# mainBoard1.net
KiCad netlist of a schematic drawn in EAGLE
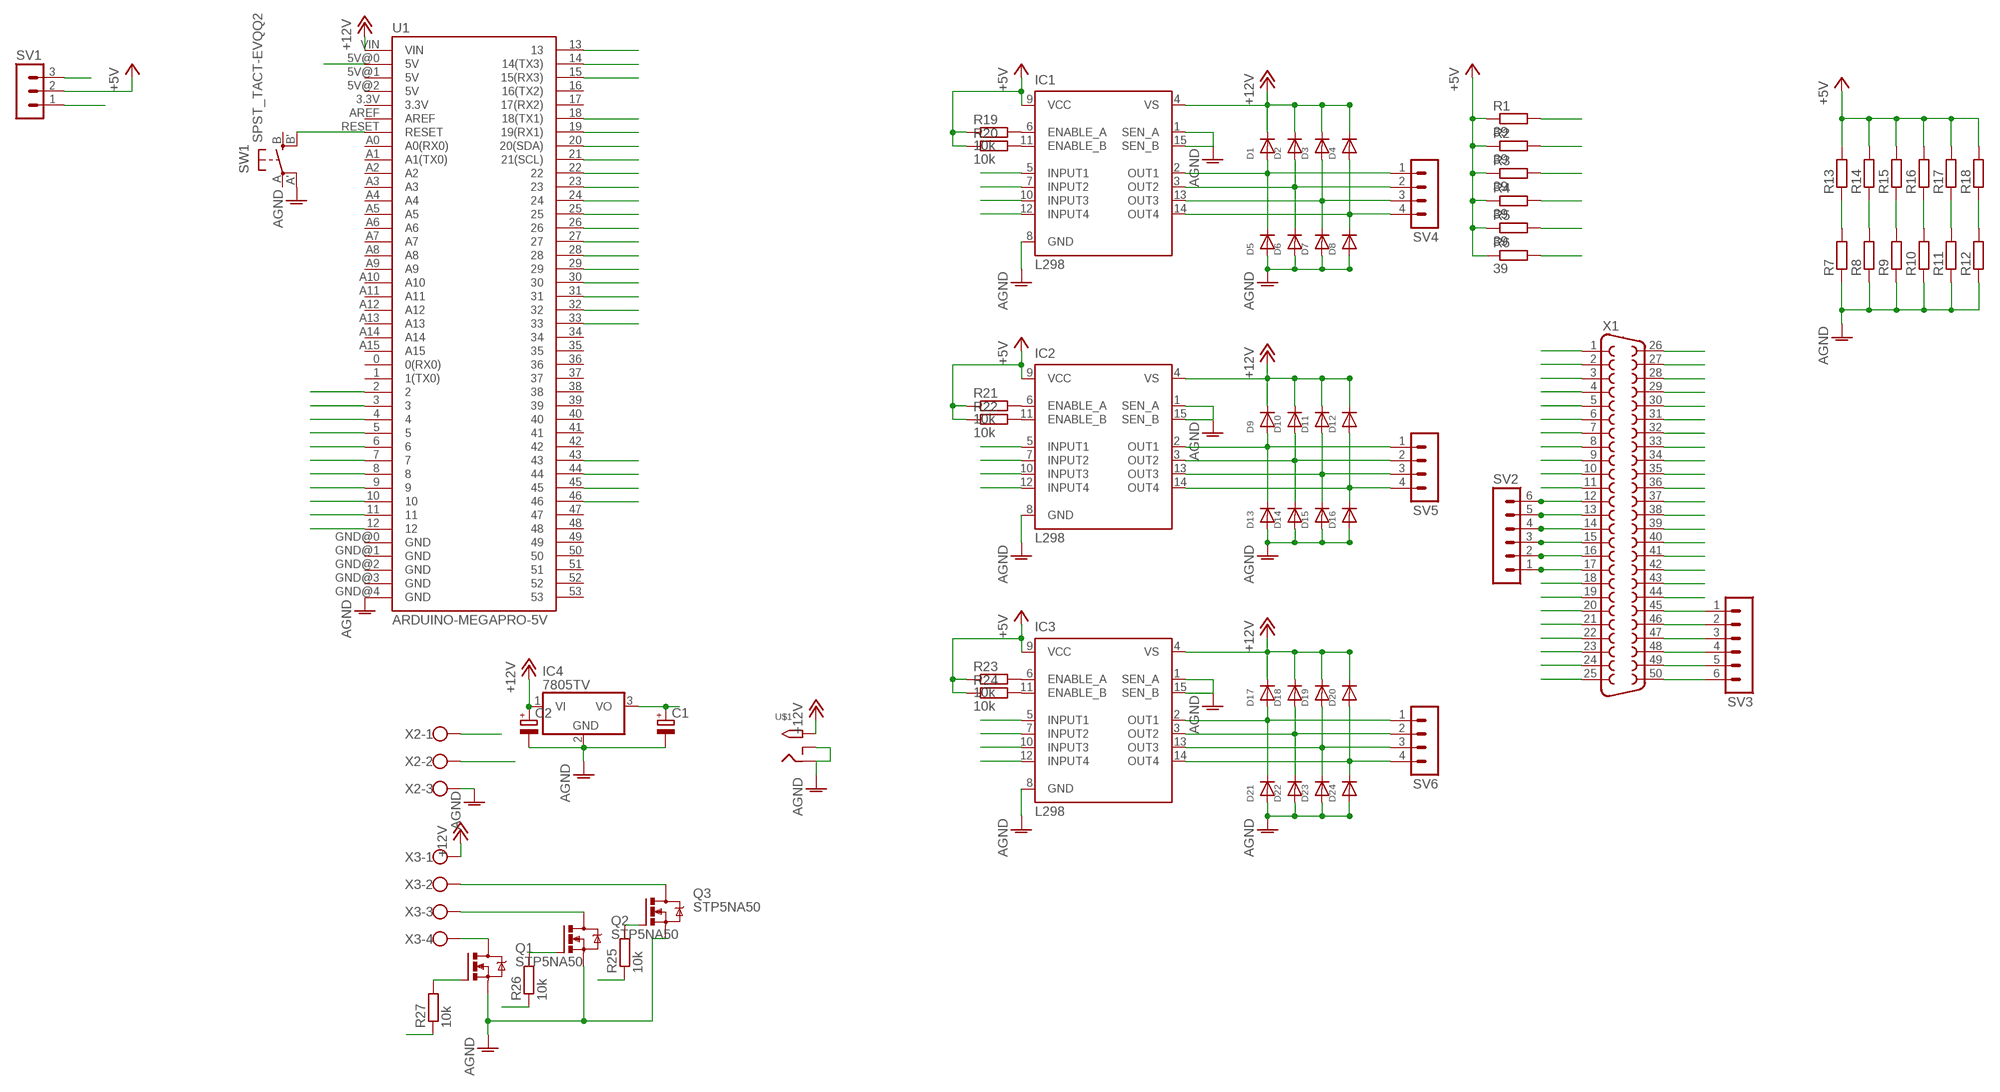
[diagram p0: schematic, sheet 1]

(export (version "E")
  (design (tool "Eeschema 10.0.6"))
  (components
    (comp (ref "C1")
      (value "CPOL-EUE2,5-6E")
      (footprint "eagle-import:E2,5-6E")
      (libsource (lib "eagle-import") (part "CPOL-EUE2,5-6E"))
    )
    (comp (ref "C2")
      (value "CPOL-EUE2,5-6E")
      (footprint "eagle-import:E2,5-6E")
      (libsource (lib "eagle-import") (part "CPOL-EUE2,5-6E"))
    )
    (comp (ref "D1")
      (value "DIODESOD-323F")
      (footprint "eagle-import:SOD-323F")
      (libsource (lib "eagle-import") (part "DIODESOD-323F"))
    )
    (comp (ref "D2")
      (value "DIODESOD-323F")
      (footprint "eagle-import:SOD-323F")
      (libsource (lib "eagle-import") (part "DIODESOD-323F"))
    )
    (comp (ref "D3")
      (value "DIODESOD-323F")
      (footprint "eagle-import:SOD-323F")
      (libsource (lib "eagle-import") (part "DIODESOD-323F"))
    )
    (comp (ref "D4")
      (value "DIODESOD-323F")
      (footprint "eagle-import:SOD-323F")
      (libsource (lib "eagle-import") (part "DIODESOD-323F"))
    )
    (comp (ref "D5")
      (value "DIODESOD-323F")
      (footprint "eagle-import:SOD-323F")
      (libsource (lib "eagle-import") (part "DIODESOD-323F"))
    )
    (comp (ref "D6")
      (value "DIODESOD-323F")
      (footprint "eagle-import:SOD-323F")
      (libsource (lib "eagle-import") (part "DIODESOD-323F"))
    )
    (comp (ref "D7")
      (value "DIODESOD-323F")
      (footprint "eagle-import:SOD-323F")
      (libsource (lib "eagle-import") (part "DIODESOD-323F"))
    )
    (comp (ref "D8")
      (value "DIODESOD-323F")
      (footprint "eagle-import:SOD-323F")
      (libsource (lib "eagle-import") (part "DIODESOD-323F"))
    )
    (comp (ref "D9")
      (value "DIODESOD-323F")
      (footprint "eagle-import:SOD-323F")
      (libsource (lib "eagle-import") (part "DIODESOD-323F"))
    )
    (comp (ref "D10")
      (value "DIODESOD-323F")
      (footprint "eagle-import:SOD-323F")
      (libsource (lib "eagle-import") (part "DIODESOD-323F"))
    )
    (comp (ref "D11")
      (value "DIODESOD-323F")
      (footprint "eagle-import:SOD-323F")
      (libsource (lib "eagle-import") (part "DIODESOD-323F"))
    )
    (comp (ref "D12")
      (value "DIODESOD-323F")
      (footprint "eagle-import:SOD-323F")
      (libsource (lib "eagle-import") (part "DIODESOD-323F"))
    )
    (comp (ref "D13")
      (value "DIODESOD-323F")
      (footprint "eagle-import:SOD-323F")
      (libsource (lib "eagle-import") (part "DIODESOD-323F"))
    )
    (comp (ref "D14")
      (value "DIODESOD-323F")
      (footprint "eagle-import:SOD-323F")
      (libsource (lib "eagle-import") (part "DIODESOD-323F"))
    )
    (comp (ref "D15")
      (value "DIODESOD-323F")
      (footprint "eagle-import:SOD-323F")
      (libsource (lib "eagle-import") (part "DIODESOD-323F"))
    )
    (comp (ref "D16")
      (value "DIODESOD-323F")
      (footprint "eagle-import:SOD-323F")
      (libsource (lib "eagle-import") (part "DIODESOD-323F"))
    )
    (comp (ref "D17")
      (value "DIODESOD-323F")
      (footprint "eagle-import:SOD-323F")
      (libsource (lib "eagle-import") (part "DIODESOD-323F"))
    )
    (comp (ref "D18")
      (value "DIODESOD-323F")
      (footprint "eagle-import:SOD-323F")
      (libsource (lib "eagle-import") (part "DIODESOD-323F"))
    )
    (comp (ref "D19")
      (value "DIODESOD-323F")
      (footprint "eagle-import:SOD-323F")
      (libsource (lib "eagle-import") (part "DIODESOD-323F"))
    )
    (comp (ref "D20")
      (value "DIODESOD-323F")
      (footprint "eagle-import:SOD-323F")
      (libsource (lib "eagle-import") (part "DIODESOD-323F"))
    )
    (comp (ref "D21")
      (value "DIODESOD-323F")
      (footprint "eagle-import:SOD-323F")
      (libsource (lib "eagle-import") (part "DIODESOD-323F"))
    )
    (comp (ref "D22")
      (value "DIODESOD-323F")
      (footprint "eagle-import:SOD-323F")
      (libsource (lib "eagle-import") (part "DIODESOD-323F"))
    )
    (comp (ref "D23")
      (value "DIODESOD-323F")
      (footprint "eagle-import:SOD-323F")
      (libsource (lib "eagle-import") (part "DIODESOD-323F"))
    )
    (comp (ref "D24")
      (value "DIODESOD-323F")
      (footprint "eagle-import:SOD-323F")
      (libsource (lib "eagle-import") (part "DIODESOD-323F"))
    )
    (comp (ref "IC1")
      (value "L298")
      (footprint "eagle-import:MULTIWATT-15")
      (fields (field (name "MPN") "L298N"))
      (libsource (lib "eagle-import") (part "L298"))
    )
    (comp (ref "IC2")
      (value "L298")
      (footprint "eagle-import:MULTIWATT-15")
      (fields (field (name "MPN") "L298N"))
      (libsource (lib "eagle-import") (part "L298"))
    )
    (comp (ref "IC3")
      (value "L298")
      (footprint "eagle-import:MULTIWATT-15")
      (fields (field (name "MPN") "L298N"))
      (libsource (lib "eagle-import") (part "L298"))
    )
    (comp (ref "IC4")
      (value "7805TV")
      (footprint "eagle-import:TO220V")
      (libsource (lib "eagle-import") (part "78TV05"))
    )
    (comp (ref "Q1")
      (value "STP5NA50")
      (footprint "eagle-import:TO220BV")
      (libsource (lib "eagle-import") (part "STP5NA50"))
    )
    (comp (ref "Q2")
      (value "STP5NA50")
      (footprint "eagle-import:TO220BV")
      (libsource (lib "eagle-import") (part "STP5NA50"))
    )
    (comp (ref "Q3")
      (value "STP5NA50")
      (footprint "eagle-import:TO220BV")
      (libsource (lib "eagle-import") (part "STP5NA50"))
    )
    (comp (ref "R1")
      (value "39")
      (footprint "eagle-import:0207_10")
      (libsource (lib "eagle-import") (part "R0207/10"))
    )
    (comp (ref "R2")
      (value "39")
      (footprint "eagle-import:0207_10")
      (libsource (lib "eagle-import") (part "R0207/10"))
    )
    (comp (ref "R3")
      (value "39")
      (footprint "eagle-import:0207_10")
      (libsource (lib "eagle-import") (part "R0207/10"))
    )
    (comp (ref "R4")
      (value "39")
      (footprint "eagle-import:0207_10")
      (libsource (lib "eagle-import") (part "R0207/10"))
    )
    (comp (ref "R5")
      (value "39")
      (footprint "eagle-import:0207_10")
      (libsource (lib "eagle-import") (part "R0207/10"))
    )
    (comp (ref "R6")
      (value "39")
      (footprint "eagle-import:0207_10")
      (libsource (lib "eagle-import") (part "R0207/10"))
    )
    (comp (ref "R7")
      (value "R0207/10")
      (footprint "eagle-import:0207_10")
      (libsource (lib "eagle-import") (part "R0207/10"))
    )
    (comp (ref "R8")
      (value "R0207/10")
      (footprint "eagle-import:0207_10")
      (libsource (lib "eagle-import") (part "R0207/10"))
    )
    (comp (ref "R9")
      (value "R0207/10")
      (footprint "eagle-import:0207_10")
      (libsource (lib "eagle-import") (part "R0207/10"))
    )
    (comp (ref "R10")
      (value "R0207/10")
      (footprint "eagle-import:0207_10")
      (libsource (lib "eagle-import") (part "R0207/10"))
    )
    (comp (ref "R11")
      (value "R0207/10")
      (footprint "eagle-import:0207_10")
      (libsource (lib "eagle-import") (part "R0207/10"))
    )
    (comp (ref "R12")
      (value "R0207/10")
      (footprint "eagle-import:0207_10")
      (libsource (lib "eagle-import") (part "R0207/10"))
    )
    (comp (ref "R13")
      (value "R0207/10")
      (footprint "eagle-import:0207_10")
      (libsource (lib "eagle-import") (part "R0207/10"))
    )
    (comp (ref "R14")
      (value "R0207/10")
      (footprint "eagle-import:0207_10")
      (libsource (lib "eagle-import") (part "R0207/10"))
    )
    (comp (ref "R15")
      (value "R0207/10")
      (footprint "eagle-import:0207_10")
      (libsource (lib "eagle-import") (part "R0207/10"))
    )
    (comp (ref "R16")
      (value "R0207/10")
      (footprint "eagle-import:0207_10")
      (libsource (lib "eagle-import") (part "R0207/10"))
    )
    (comp (ref "R17")
      (value "R0207/10")
      (footprint "eagle-import:0207_10")
      (libsource (lib "eagle-import") (part "R0207/10"))
    )
    (comp (ref "R18")
      (value "R0207/10")
      (footprint "eagle-import:0207_10")
      (libsource (lib "eagle-import") (part "R0207/10"))
    )
    (comp (ref "R19")
      (value "10k")
      (footprint "eagle-import:R0805")
      (libsource (lib "eagle-import") (part "R-EU_R0805"))
    )
    (comp (ref "R20")
      (value "10k")
      (footprint "eagle-import:R0805")
      (libsource (lib "eagle-import") (part "R-EU_R0805"))
    )
    (comp (ref "R21")
      (value "10k")
      (footprint "eagle-import:R0805")
      (libsource (lib "eagle-import") (part "R-EU_R0805"))
    )
    (comp (ref "R22")
      (value "10k")
      (footprint "eagle-import:R0805")
      (libsource (lib "eagle-import") (part "R-EU_R0805"))
    )
    (comp (ref "R23")
      (value "10k")
      (footprint "eagle-import:R0805")
      (libsource (lib "eagle-import") (part "R-EU_R0805"))
    )
    (comp (ref "R24")
      (value "10k")
      (footprint "eagle-import:R0805")
      (libsource (lib "eagle-import") (part "R-EU_R0805"))
    )
    (comp (ref "R25")
      (value "10k")
      (footprint "eagle-import:R0805")
      (libsource (lib "eagle-import") (part "R-EU_R0805"))
    )
    (comp (ref "R26")
      (value "10k")
      (footprint "eagle-import:R0805")
      (libsource (lib "eagle-import") (part "R-EU_R0805"))
    )
    (comp (ref "R27")
      (value "10k")
      (footprint "eagle-import:R0805")
      (libsource (lib "eagle-import") (part "R-EU_R0805"))
    )
    (comp (ref "SV1")
      (value "MA03-1")
      (footprint "eagle-import:MA03-1")
      (libsource (lib "eagle-import") (part "MA03-1"))
    )
    (comp (ref "SV2")
      (value "MA06-1")
      (footprint "eagle-import:MA06-1")
      (libsource (lib "eagle-import") (part "MA06-1"))
    )
    (comp (ref "SV3")
      (value "MA06-1")
      (footprint "eagle-import:MA06-1")
      (libsource (lib "eagle-import") (part "MA06-1"))
    )
    (comp (ref "SV4")
      (value "MA04-1")
      (footprint "eagle-import:MA04-1")
      (libsource (lib "eagle-import") (part "MA04-1"))
    )
    (comp (ref "SV5")
      (value "MA04-1")
      (footprint "eagle-import:MA04-1")
      (libsource (lib "eagle-import") (part "MA04-1"))
    )
    (comp (ref "SV6")
      (value "MA04-1")
      (footprint "eagle-import:MA04-1")
      (libsource (lib "eagle-import") (part "MA04-1"))
    )
    (comp (ref "SW1")
      (value "SPST_TACT-EVQQ2")
      (footprint "eagle-import:EVQ-Q2")
      (libsource (lib "eagle-import") (part "SPST_TACT-EVQQ2"))
    )
    (comp (ref "U$1")
      (value "2.1MMJACKTHM")
      (footprint "eagle-import:PJ-102A")
      (libsource (lib "eagle-import") (part "2.1MMJACKTHM"))
    )
    (comp (ref "U1")
      (value "ARDUINO-MEGAPRO-5V")
      (footprint "eagle-import:ARDUINO_MEGA-PRO-5V")
      (libsource (lib "eagle-import") (part "ARDUINO-MEGAPRO-5V"))
    )
    (comp (ref "X1")
      (value "F50VP")
      (footprint "eagle-import:F50VP")
      (libsource (lib "eagle-import") (part "F50VP"))
    )
    (comp (ref "X2")
      (value "W237-103")
      (footprint "eagle-import:W237-103")
      (fields (field (name "MPN") "237-103"))
      (libsource (lib "eagle-import") (part "W237-103"))
    )
    (comp (ref "X3")
      (value "W237-4")
      (footprint "eagle-import:W237-4")
      (libsource (lib "eagle-import") (part "W237-4"))
    )
  )
  (nets
    (net (code "1") (name "+5V") (class "Default")
      (node (ref "IC1") (pin "9") (pinfunction "VCC_9") (pintype "power_in"))
      (node (ref "IC2") (pin "9") (pinfunction "VCC_9") (pintype "power_in"))
      (node (ref "IC3") (pin "9") (pinfunction "VCC_9") (pintype "power_in"))
      (node (ref "R1") (pin "1") (pinfunction "1_1") (pintype "passive"))
      (node (ref "R13") (pin "2") (pinfunction "2_2") (pintype "passive"))
      (node (ref "R14") (pin "2") (pinfunction "2_2") (pintype "passive"))
      (node (ref "R15") (pin "2") (pinfunction "2_2") (pintype "passive"))
      (node (ref "R16") (pin "2") (pinfunction "2_2") (pintype "passive"))
      (node (ref "R17") (pin "2") (pinfunction "2_2") (pintype "passive"))
      (node (ref "R18") (pin "2") (pinfunction "2_2") (pintype "passive"))
      (node (ref "R19") (pin "1") (pinfunction "1_1") (pintype "passive"))
      (node (ref "R2") (pin "1") (pinfunction "1_1") (pintype "passive"))
      (node (ref "R20") (pin "1") (pinfunction "1_1") (pintype "passive"))
      (node (ref "R21") (pin "1") (pinfunction "1_1") (pintype "passive"))
      (node (ref "R22") (pin "1") (pinfunction "1_1") (pintype "passive"))
      (node (ref "R23") (pin "1") (pinfunction "1_1") (pintype "passive"))
      (node (ref "R24") (pin "1") (pinfunction "1_1") (pintype "passive"))
      (node (ref "R3") (pin "1") (pinfunction "1_1") (pintype "passive"))
      (node (ref "R4") (pin "1") (pinfunction "1_1") (pintype "passive"))
      (node (ref "R5") (pin "1") (pinfunction "1_1") (pintype "passive"))
      (node (ref "R6") (pin "1") (pinfunction "1_1") (pintype "passive"))
      (node (ref "SV1") (pin "2") (pinfunction "2_2") (pintype "passive"))
    )
    (net (code "2") (name "+12V") (class "Default")
      (node (ref "C2") (pin "+") (pinfunction "+_+") (pintype "passive"))
      (node (ref "D1") (pin "C") (pinfunction "C_C") (pintype "passive"))
      (node (ref "D10") (pin "C") (pinfunction "C_C") (pintype "passive"))
      (node (ref "D11") (pin "C") (pinfunction "C_C") (pintype "passive"))
      (node (ref "D12") (pin "C") (pinfunction "C_C") (pintype "passive"))
      (node (ref "D17") (pin "C") (pinfunction "C_C") (pintype "passive"))
      (node (ref "D18") (pin "C") (pinfunction "C_C") (pintype "passive"))
      (node (ref "D19") (pin "C") (pinfunction "C_C") (pintype "passive"))
      (node (ref "D2") (pin "C") (pinfunction "C_C") (pintype "passive"))
      (node (ref "D20") (pin "C") (pinfunction "C_C") (pintype "passive"))
      (node (ref "D3") (pin "C") (pinfunction "C_C") (pintype "passive"))
      (node (ref "D4") (pin "C") (pinfunction "C_C") (pintype "passive"))
      (node (ref "D9") (pin "C") (pinfunction "C_C") (pintype "passive"))
      (node (ref "IC1") (pin "4") (pinfunction "VS_4") (pintype "power_in"))
      (node (ref "IC2") (pin "4") (pinfunction "VS_4") (pintype "power_in"))
      (node (ref "IC3") (pin "4") (pinfunction "VS_4") (pintype "power_in"))
      (node (ref "IC4") (pin "1") (pinfunction "VI_1") (pintype "input"))
      (node (ref "U$1") (pin "TIP") (pinfunction "TIP_TIP") (pintype "bidirectional"))
      (node (ref "U1") (pin "VIN") (pinfunction "VIN_VIN") (pintype "bidirectional"))
      (node (ref "X3") (pin "1") (pinfunction "KL_1") (pintype "passive"))
    )
    (net (code "3") (name "/5V_ARD") (class "Default")
      (node (ref "SV1") (pin "3") (pinfunction "3_3") (pintype "passive"))
      (node (ref "U1") (pin "5V@0") (pinfunction "5V_5V@0") (pintype "bidirectional"))
    )
    (net (code "4") (name "/5V_REG") (class "Default")
      (node (ref "C1") (pin "+") (pinfunction "+_+") (pintype "passive"))
      (node (ref "IC4") (pin "3") (pinfunction "VO_3") (pintype "passive"))
      (node (ref "SV1") (pin "1") (pinfunction "1_1") (pintype "passive"))
      (node (ref "X2") (pin "1") (pinfunction "KL_1") (pintype "passive"))
    )
    (net (code "5") (name "/LED_0") (class "Default")
      (node (ref "R1") (pin "2") (pinfunction "2_2") (pintype "passive"))
      (node (ref "X1") (pin "11") (pinfunction "11_11") (pintype "passive"))
    )
    (net (code "6") (name "/LED_1") (class "Default")
      (node (ref "R2") (pin "2") (pinfunction "2_2") (pintype "passive"))
      (node (ref "X1") (pin "27") (pinfunction "27_27") (pintype "passive"))
    )
    (net (code "7") (name "/LED_2") (class "Default")
      (node (ref "R3") (pin "2") (pinfunction "2_2") (pintype "passive"))
      (node (ref "X1") (pin "10") (pinfunction "10_10") (pintype "passive"))
    )
    (net (code "8") (name "/LED_3") (class "Default")
      (node (ref "R4") (pin "2") (pinfunction "2_2") (pintype "passive"))
      (node (ref "X1") (pin "26") (pinfunction "26_26") (pintype "passive"))
    )
    (net (code "9") (name "/LED_4") (class "Default")
      (node (ref "R5") (pin "2") (pinfunction "2_2") (pintype "passive"))
      (node (ref "X1") (pin "9") (pinfunction "9_9") (pintype "passive"))
    )
    (net (code "10") (name "/LED_5") (class "Default")
      (node (ref "R6") (pin "2") (pinfunction "2_2") (pintype "passive"))
      (node (ref "X1") (pin "25") (pinfunction "25_25") (pintype "passive"))
    )
    (net (code "11") (name "/LED_B") (class "Default")
      (node (ref "R27") (pin "1") (pinfunction "1_1") (pintype "passive"))
      (node (ref "U1") (pin "46") (pinfunction "46_46") (pintype "bidirectional"))
    )
    (net (code "12") (name "/LED_DATA") (class "Default")
      (node (ref "U1") (pin "43") (pinfunction "43_43") (pintype "bidirectional"))
      (node (ref "X2") (pin "2") (pinfunction "KL_2") (pintype "passive"))
    )
    (net (code "13") (name "/LED_G") (class "Default")
      (node (ref "R26") (pin "1") (pinfunction "1_1") (pintype "passive"))
      (node (ref "U1") (pin "45") (pinfunction "45_45") (pintype "bidirectional"))
    )
    (net (code "14") (name "/LED_R") (class "Default")
      (node (ref "R25") (pin "1") (pinfunction "1_1") (pintype "passive"))
      (node (ref "U1") (pin "44") (pinfunction "44_44") (pintype "bidirectional"))
    )
    (net (code "15") (name "/M1_0") (class "Default")
      (node (ref "D1") (pin "A") (pinfunction "A_A") (pintype "passive"))
      (node (ref "D5") (pin "C") (pinfunction "C_C") (pintype "passive"))
      (node (ref "IC1") (pin "2") (pinfunction "OUT1_2") (pintype "output"))
      (node (ref "SV3") (pin "6") (pinfunction "6_6") (pintype "passive"))
      (node (ref "SV4") (pin "1") (pinfunction "1_1") (pintype "passive"))
      (node (ref "X1") (pin "50") (pinfunction "50_50") (pintype "passive"))
    )
    (net (code "16") (name "/M1_0_IN") (class "Default")
      (node (ref "IC1") (pin "5") (pinfunction "INPUT1_5") (pintype "input"))
      (node (ref "U1") (pin "14") (pinfunction "14(TX3)_14") (pintype "bidirectional"))
    )
    (net (code "17") (name "/M1_1") (class "Default")
      (node (ref "D3") (pin "A") (pinfunction "A_A") (pintype "passive"))
      (node (ref "D7") (pin "C") (pinfunction "C_C") (pintype "passive"))
      (node (ref "IC1") (pin "13") (pinfunction "OUT3_13") (pintype "output"))
      (node (ref "SV3") (pin "5") (pinfunction "5_5") (pintype "passive"))
      (node (ref "SV4") (pin "3") (pinfunction "3_3") (pintype "passive"))
      (node (ref "X1") (pin "49") (pinfunction "49_49") (pintype "passive"))
    )
    (net (code "18") (name "/M1_1_IN") (class "Default")
      (node (ref "IC1") (pin "10") (pinfunction "INPUT3_10") (pintype "input"))
      (node (ref "U1") (pin "4") (pinfunction "4_4") (pintype "bidirectional"))
    )
    (net (code "19") (name "/M1_2") (class "Default")
      (node (ref "D13") (pin "C") (pinfunction "C_C") (pintype "passive"))
      (node (ref "D9") (pin "A") (pinfunction "A_A") (pintype "passive"))
      (node (ref "IC2") (pin "2") (pinfunction "OUT1_2") (pintype "output"))
      (node (ref "SV3") (pin "4") (pinfunction "4_4") (pintype "passive"))
      (node (ref "SV5") (pin "1") (pinfunction "1_1") (pintype "passive"))
      (node (ref "X1") (pin "48") (pinfunction "48_48") (pintype "passive"))
    )
    (net (code "20") (name "/M1_2_IN") (class "Default")
      (node (ref "IC2") (pin "5") (pinfunction "INPUT1_5") (pintype "input"))
      (node (ref "U1") (pin "6") (pinfunction "6_6") (pintype "bidirectional"))
    )
    (net (code "21") (name "/M1_3") (class "Default")
      (node (ref "D11") (pin "A") (pinfunction "A_A") (pintype "passive"))
      (node (ref "D15") (pin "C") (pinfunction "C_C") (pintype "passive"))
      (node (ref "IC2") (pin "13") (pinfunction "OUT3_13") (pintype "output"))
      (node (ref "SV3") (pin "3") (pinfunction "3_3") (pintype "passive"))
      (node (ref "SV5") (pin "3") (pinfunction "3_3") (pintype "passive"))
      (node (ref "X1") (pin "47") (pinfunction "47_47") (pintype "passive"))
    )
    (net (code "22") (name "/M1_3_IN") (class "Default")
      (node (ref "IC2") (pin "10") (pinfunction "INPUT3_10") (pintype "input"))
      (node (ref "U1") (pin "8") (pinfunction "8_8") (pintype "bidirectional"))
    )
    (net (code "23") (name "/M1_4") (class "Default")
      (node (ref "D17") (pin "A") (pinfunction "A_A") (pintype "passive"))
      (node (ref "D21") (pin "C") (pinfunction "C_C") (pintype "passive"))
      (node (ref "IC3") (pin "2") (pinfunction "OUT1_2") (pintype "output"))
      (node (ref "SV3") (pin "2") (pinfunction "2_2") (pintype "passive"))
      (node (ref "SV6") (pin "1") (pinfunction "1_1") (pintype "passive"))
      (node (ref "X1") (pin "46") (pinfunction "46_46") (pintype "passive"))
    )
    (net (code "24") (name "/M1_4_IN") (class "Default")
      (node (ref "IC3") (pin "5") (pinfunction "INPUT1_5") (pintype "input"))
      (node (ref "U1") (pin "10") (pinfunction "10_10") (pintype "bidirectional"))
    )
    (net (code "25") (name "/M1_5") (class "Default")
      (node (ref "D19") (pin "A") (pinfunction "A_A") (pintype "passive"))
      (node (ref "D23") (pin "C") (pinfunction "C_C") (pintype "passive"))
      (node (ref "IC3") (pin "13") (pinfunction "OUT3_13") (pintype "output"))
      (node (ref "SV3") (pin "1") (pinfunction "1_1") (pintype "passive"))
      (node (ref "SV6") (pin "3") (pinfunction "3_3") (pintype "passive"))
      (node (ref "X1") (pin "45") (pinfunction "45_45") (pintype "passive"))
    )
    (net (code "26") (name "/M1_5_IN") (class "Default")
      (node (ref "IC3") (pin "10") (pinfunction "INPUT3_10") (pintype "input"))
      (node (ref "U1") (pin "12") (pinfunction "12_12") (pintype "bidirectional"))
    )
    (net (code "27") (name "/M2_0") (class "Default")
      (node (ref "D2") (pin "A") (pinfunction "A_A") (pintype "passive"))
      (node (ref "D6") (pin "C") (pinfunction "C_C") (pintype "passive"))
      (node (ref "IC1") (pin "3") (pinfunction "OUT2_3") (pintype "output"))
      (node (ref "SV2") (pin "1") (pinfunction "1_1") (pintype "passive"))
      (node (ref "SV4") (pin "2") (pinfunction "2_2") (pintype "passive"))
      (node (ref "X1") (pin "17") (pinfunction "17_17") (pintype "passive"))
    )
    (net (code "28") (name "/M2_0_IN") (class "Default")
      (node (ref "IC1") (pin "7") (pinfunction "INPUT2_7") (pintype "input"))
      (node (ref "U1") (pin "15") (pinfunction "15(RX3)_15") (pintype "bidirectional"))
    )
    (net (code "29") (name "/M2_1") (class "Default")
      (node (ref "D4") (pin "A") (pinfunction "A_A") (pintype "passive"))
      (node (ref "D8") (pin "C") (pinfunction "C_C") (pintype "passive"))
      (node (ref "IC1") (pin "14") (pinfunction "OUT4_14") (pintype "output"))
      (node (ref "SV2") (pin "2") (pinfunction "2_2") (pintype "passive"))
      (node (ref "SV4") (pin "4") (pinfunction "4_4") (pintype "passive"))
      (node (ref "X1") (pin "16") (pinfunction "16_16") (pintype "passive"))
    )
    (net (code "30") (name "/M2_1_IN") (class "Default")
      (node (ref "IC1") (pin "12") (pinfunction "INPUT4_12") (pintype "input"))
      (node (ref "U1") (pin "5") (pinfunction "5_5") (pintype "bidirectional"))
    )
    (net (code "31") (name "/M2_2") (class "Default")
      (node (ref "D10") (pin "A") (pinfunction "A_A") (pintype "passive"))
      (node (ref "D14") (pin "C") (pinfunction "C_C") (pintype "passive"))
      (node (ref "IC2") (pin "3") (pinfunction "OUT2_3") (pintype "output"))
      (node (ref "SV2") (pin "3") (pinfunction "3_3") (pintype "passive"))
      (node (ref "SV5") (pin "2") (pinfunction "2_2") (pintype "passive"))
      (node (ref "X1") (pin "15") (pinfunction "15_15") (pintype "passive"))
    )
    (net (code "32") (name "/M2_2_IN") (class "Default")
      (node (ref "IC2") (pin "7") (pinfunction "INPUT2_7") (pintype "input"))
      (node (ref "U1") (pin "7") (pinfunction "7_7") (pintype "bidirectional"))
    )
    (net (code "33") (name "/M2_3") (class "Default")
      (node (ref "D12") (pin "A") (pinfunction "A_A") (pintype "passive"))
      (node (ref "D16") (pin "C") (pinfunction "C_C") (pintype "passive"))
      (node (ref "IC2") (pin "14") (pinfunction "OUT4_14") (pintype "output"))
      (node (ref "SV2") (pin "4") (pinfunction "4_4") (pintype "passive"))
      (node (ref "SV5") (pin "4") (pinfunction "4_4") (pintype "passive"))
      (node (ref "X1") (pin "14") (pinfunction "14_14") (pintype "passive"))
    )
    (net (code "34") (name "/M2_3_IN") (class "Default")
      (node (ref "IC2") (pin "12") (pinfunction "INPUT4_12") (pintype "input"))
      (node (ref "U1") (pin "9") (pinfunction "9_9") (pintype "bidirectional"))
    )
    (net (code "35") (name "/M2_4") (class "Default")
      (node (ref "D18") (pin "A") (pinfunction "A_A") (pintype "passive"))
      (node (ref "D22") (pin "C") (pinfunction "C_C") (pintype "passive"))
      (node (ref "IC3") (pin "3") (pinfunction "OUT2_3") (pintype "output"))
      (node (ref "SV2") (pin "5") (pinfunction "5_5") (pintype "passive"))
      (node (ref "SV6") (pin "2") (pinfunction "2_2") (pintype "passive"))
      (node (ref "X1") (pin "13") (pinfunction "13_13") (pintype "passive"))
    )
    (net (code "36") (name "/M2_4_IN") (class "Default")
      (node (ref "IC3") (pin "7") (pinfunction "INPUT2_7") (pintype "input"))
      (node (ref "U1") (pin "11") (pinfunction "11_11") (pintype "bidirectional"))
    )
    (net (code "37") (name "/M2_5") (class "Default")
      (node (ref "D20") (pin "A") (pinfunction "A_A") (pintype "passive"))
      (node (ref "D24") (pin "C") (pinfunction "C_C") (pintype "passive"))
      (node (ref "IC3") (pin "14") (pinfunction "OUT4_14") (pintype "output"))
      (node (ref "SV2") (pin "6") (pinfunction "6_6") (pintype "passive"))
      (node (ref "SV6") (pin "4") (pinfunction "4_4") (pintype "passive"))
      (node (ref "X1") (pin "12") (pinfunction "12_12") (pintype "passive"))
    )
    (net (code "38") (name "/M2_5_IN") (class "Default")
      (node (ref "IC3") (pin "12") (pinfunction "INPUT4_12") (pintype "input"))
      (node (ref "U1") (pin "13") (pinfunction "13_13") (pintype "bidirectional"))
    )
    (net (code "39") (name "/MS_0") (class "Default")
      (node (ref "R13") (pin "1") (pinfunction "1_1") (pintype "passive"))
      (node (ref "R7") (pin "2") (pinfunction "2_2") (pintype "passive"))
      (node (ref "U1") (pin "2") (pinfunction "2_2") (pintype "bidirectional"))
      (node (ref "X1") (pin "23") (pinfunction "23_23") (pintype "passive"))
    )
    (net (code "40") (name "/MS_1") (class "Default")
      (node (ref "R14") (pin "1") (pinfunction "1_1") (pintype "passive"))
      (node (ref "R8") (pin "2") (pinfunction "2_2") (pintype "passive"))
      (node (ref "U1") (pin "3") (pinfunction "3_3") (pintype "bidirectional"))
      (node (ref "X1") (pin "7") (pinfunction "7_7") (pintype "passive"))
    )
    (net (code "41") (name "/MS_2") (class "Default")
      (node (ref "R15") (pin "1") (pinfunction "1_1") (pintype "passive"))
      (node (ref "R9") (pin "2") (pinfunction "2_2") (pintype "passive"))
      (node (ref "U1") (pin "21") (pinfunction "21(SCL)_21") (pintype "bidirectional"))
      (node (ref "X1") (pin "24") (pinfunction "24_24") (pintype "passive"))
    )
    (net (code "42") (name "/MS_3") (class "Default")
      (node (ref "R10") (pin "2") (pinfunction "2_2") (pintype "passive"))
      (node (ref "R16") (pin "1") (pinfunction "1_1") (pintype "passive"))
      (node (ref "U1") (pin "20") (pinfunction "20(SDA)_20") (pintype "bidirectional"))
      (node (ref "X1") (pin "8") (pinfunction "8_8") (pintype "passive"))
    )
    (net (code "43") (name "/MS_4") (class "Default")
      (node (ref "R11") (pin "2") (pinfunction "2_2") (pintype "passive"))
      (node (ref "R17") (pin "1") (pinfunction "1_1") (pintype "passive"))
      (node (ref "U1") (pin "19") (pinfunction "19(RX1)_19") (pintype "bidirectional"))
      (node (ref "X1") (pin "6") (pinfunction "6_6") (pintype "passive"))
    )
    (net (code "44") (name "/MS_5") (class "Default")
      (node (ref "R12") (pin "2") (pinfunction "2_2") (pintype "passive"))
      (node (ref "R18") (pin "1") (pinfunction "1_1") (pintype "passive"))
      (node (ref "U1") (pin "18") (pinfunction "18(TX1)_18") (pintype "bidirectional"))
      (node (ref "X1") (pin "22") (pinfunction "22_22") (pintype "passive"))
    )
    (net (code "45") (name "/P0_0") (class "Default")
      (node (ref "U1") (pin "22") (pinfunction "22_22") (pintype "bidirectional"))
      (node (ref "X1") (pin "2") (pinfunction "2_2") (pintype "passive"))
    )
    (net (code "46") (name "/P0_1") (class "Default")
      (node (ref "U1") (pin "24") (pinfunction "24_24") (pintype "bidirectional"))
      (node (ref "X1") (pin "1") (pinfunction "1_1") (pintype "passive"))
    )
    (net (code "47") (name "/P0_2") (class "Default")
      (node (ref "U1") (pin "26") (pinfunction "26_26") (pintype "bidirectional"))
      (node (ref "X1") (pin "36") (pinfunction "36_36") (pintype "passive"))
    )
    (net (code "48") (name "/P0_3") (class "Default")
      (node (ref "U1") (pin "28") (pinfunction "28_28") (pintype "bidirectional"))
      (node (ref "X1") (pin "35") (pinfunction "35_35") (pintype "passive"))
    )
    (net (code "49") (name "/P0_4") (class "Default")
      (node (ref "U1") (pin "30") (pinfunction "30_30") (pintype "bidirectional"))
      (node (ref "X1") (pin "18") (pinfunction "18_18") (pintype "passive"))
    )
    (net (code "50") (name "/P0_5") (class "Default")
      (node (ref "U1") (pin "32") (pinfunction "32_32") (pintype "bidirectional"))
      (node (ref "X1") (pin "34") (pinfunction "34_34") (pintype "passive"))
    )
    (net (code "51") (name "/P1_0") (class "Default")
      (node (ref "U1") (pin "23") (pinfunction "23_23") (pintype "bidirectional"))
      (node (ref "X1") (pin "5") (pinfunction "5_5") (pintype "passive"))
    )
    (net (code "52") (name "/P1_1") (class "Default")
      (node (ref "U1") (pin "25") (pinfunction "25_25") (pintype "bidirectional"))
      (node (ref "X1") (pin "21") (pinfunction "21_21") (pintype "passive"))
    )
    (net (code "53") (name "/P1_2") (class "Default")
      (node (ref "U1") (pin "27") (pinfunction "27_27") (pintype "bidirectional"))
      (node (ref "X1") (pin "4") (pinfunction "4_4") (pintype "passive"))
    )
    (net (code "54") (name "/P1_3") (class "Default")
      (node (ref "U1") (pin "29") (pinfunction "29_29") (pintype "bidirectional"))
      (node (ref "X1") (pin "20") (pinfunction "20_20") (pintype "passive"))
    )
    (net (code "55") (name "/P1_4") (class "Default")
      (node (ref "U1") (pin "31") (pinfunction "31_31") (pintype "bidirectional"))
      (node (ref "X1") (pin "3") (pinfunction "3_3") (pintype "passive"))
    )
    (net (code "56") (name "/P1_5") (class "Default")
      (node (ref "U1") (pin "33") (pinfunction "33_33") (pintype "bidirectional"))
      (node (ref "X1") (pin "19") (pinfunction "19_19") (pintype "passive"))
    )
    (net (code "57") (name "AGND") (class "Default")
      (node (ref "C1") (pin "-") (pinfunction "-_-") (pintype "passive"))
      (node (ref "C2") (pin "-") (pinfunction "-_-") (pintype "passive"))
      (node (ref "D13") (pin "A") (pinfunction "A_A") (pintype "passive"))
      (node (ref "D14") (pin "A") (pinfunction "A_A") (pintype "passive"))
      (node (ref "D15") (pin "A") (pinfunction "A_A") (pintype "passive"))
      (node (ref "D16") (pin "A") (pinfunction "A_A") (pintype "passive"))
      (node (ref "D21") (pin "A") (pinfunction "A_A") (pintype "passive"))
      (node (ref "D22") (pin "A") (pinfunction "A_A") (pintype "passive"))
      (node (ref "D23") (pin "A") (pinfunction "A_A") (pintype "passive"))
      (node (ref "D24") (pin "A") (pinfunction "A_A") (pintype "passive"))
      (node (ref "D5") (pin "A") (pinfunction "A_A") (pintype "passive"))
      (node (ref "D6") (pin "A") (pinfunction "A_A") (pintype "passive"))
      (node (ref "D7") (pin "A") (pinfunction "A_A") (pintype "passive"))
      (node (ref "D8") (pin "A") (pinfunction "A_A") (pintype "passive"))
      (node (ref "IC1") (pin "1") (pinfunction "SEN_A_1") (pintype "input"))
      (node (ref "IC1") (pin "15") (pinfunction "SEN_B_15") (pintype "input"))
      (node (ref "IC1") (pin "8") (pinfunction "GND_8") (pintype "power_in"))
      (node (ref "IC2") (pin "1") (pinfunction "SEN_A_1") (pintype "input"))
      (node (ref "IC2") (pin "15") (pinfunction "SEN_B_15") (pintype "input"))
      (node (ref "IC2") (pin "8") (pinfunction "GND_8") (pintype "power_in"))
      (node (ref "IC3") (pin "1") (pinfunction "SEN_A_1") (pintype "input"))
      (node (ref "IC3") (pin "15") (pinfunction "SEN_B_15") (pintype "input"))
      (node (ref "IC3") (pin "8") (pinfunction "GND_8") (pintype "power_in"))
      (node (ref "IC4") (pin "2") (pinfunction "GND_2") (pintype "passive"))
      (node (ref "Q1") (pin "S") (pinfunction "S_S") (pintype "passive"))
      (node (ref "Q2") (pin "S") (pinfunction "S_S") (pintype "passive"))
      (node (ref "Q3") (pin "S") (pinfunction "S_S") (pintype "passive"))
      (node (ref "R10") (pin "1") (pinfunction "1_1") (pintype "passive"))
      (node (ref "R11") (pin "1") (pinfunction "1_1") (pintype "passive"))
      (node (ref "R12") (pin "1") (pinfunction "1_1") (pintype "passive"))
      (node (ref "R7") (pin "1") (pinfunction "1_1") (pintype "passive"))
      (node (ref "R8") (pin "1") (pinfunction "1_1") (pintype "passive"))
      (node (ref "R9") (pin "1") (pinfunction "1_1") (pintype "passive"))
      (node (ref "SW1") (pin "A'") (pinfunction "P1_A'") (pintype "passive"))
      (node (ref "U$1") (pin "RING") (pinfunction "RING_RING") (pintype "bidirectional"))
      (node (ref "U$1") (pin "RING_SW") (pinfunction "RING_SW_RING_SW") (pintype "bidirectional"))
      (node (ref "U1") (pin "GND@4") (pinfunction "GND_GND@4") (pintype "bidirectional"))
      (node (ref "X1") (pin "28") (pinfunction "28_28") (pintype "passive"))
      (node (ref "X1") (pin "29") (pinfunction "29_29") (pintype "passive"))
      (node (ref "X1") (pin "30") (pinfunction "30_30") (pintype "passive"))
      (node (ref "X1") (pin "31") (pinfunction "31_31") (pintype "passive"))
      (node (ref "X1") (pin "32") (pinfunction "32_32") (pintype "passive"))
      (node (ref "X1") (pin "33") (pinfunction "33_33") (pintype "passive"))
      (node (ref "X2") (pin "3") (pinfunction "KL_3") (pintype "passive"))
    )
    (net (code "58") (name "Net-(IC1-ENABLE_A)") (class "Default")
      (node (ref "IC1") (pin "6") (pinfunction "ENABLE_A_6") (pintype "input"))
      (node (ref "R19") (pin "2") (pinfunction "2_2") (pintype "passive"))
    )
    (net (code "59") (name "Net-(IC1-ENABLE_B)") (class "Default")
      (node (ref "IC1") (pin "11") (pinfunction "ENABLE_B_11") (pintype "input"))
      (node (ref "R20") (pin "2") (pinfunction "2_2") (pintype "passive"))
    )
    (net (code "60") (name "Net-(IC2-ENABLE_A)") (class "Default")
      (node (ref "IC2") (pin "6") (pinfunction "ENABLE_A_6") (pintype "input"))
      (node (ref "R21") (pin "2") (pinfunction "2_2") (pintype "passive"))
    )
    (net (code "61") (name "Net-(IC2-ENABLE_B)") (class "Default")
      (node (ref "IC2") (pin "11") (pinfunction "ENABLE_B_11") (pintype "input"))
      (node (ref "R22") (pin "2") (pinfunction "2_2") (pintype "passive"))
    )
    (net (code "62") (name "Net-(IC3-ENABLE_A)") (class "Default")
      (node (ref "IC3") (pin "6") (pinfunction "ENABLE_A_6") (pintype "input"))
      (node (ref "R23") (pin "2") (pinfunction "2_2") (pintype "passive"))
    )
    (net (code "63") (name "Net-(IC3-ENABLE_B)") (class "Default")
      (node (ref "IC3") (pin "11") (pinfunction "ENABLE_B_11") (pintype "input"))
      (node (ref "R24") (pin "2") (pinfunction "2_2") (pintype "passive"))
    )
    (net (code "64") (name "Net-(Q1-PadG)") (class "Default")
      (node (ref "Q1") (pin "G") (pinfunction "G_G") (pintype "passive"))
      (node (ref "R27") (pin "2") (pinfunction "2_2") (pintype "passive"))
    )
    (net (code "65") (name "Net-(Q2-PadG)") (class "Default")
      (node (ref "Q2") (pin "G") (pinfunction "G_G") (pintype "passive"))
      (node (ref "R26") (pin "2") (pinfunction "2_2") (pintype "passive"))
    )
    (net (code "66") (name "Net-(Q3-PadG)") (class "Default")
      (node (ref "Q3") (pin "G") (pinfunction "G_G") (pintype "passive"))
      (node (ref "R25") (pin "2") (pinfunction "2_2") (pintype "passive"))
    )
    (net (code "67") (name "Net-(SW1-S1)") (class "Default")
      (node (ref "SW1") (pin "B'") (pinfunction "S1_B'") (pintype "passive"))
      (node (ref "U1") (pin "RESET") (pinfunction "RESET_RESET") (pintype "bidirectional"))
    )
    (net (code "68") (name "Net-(X3B-KL)") (class "Default")
      (node (ref "Q3") (pin "D") (pinfunction "D_D") (pintype "passive"))
      (node (ref "X3") (pin "2") (pinfunction "KL_2") (pintype "passive"))
    )
    (net (code "69") (name "Net-(X3C-KL)") (class "Default")
      (node (ref "Q2") (pin "D") (pinfunction "D_D") (pintype "passive"))
      (node (ref "X3") (pin "3") (pinfunction "KL_3") (pintype "passive"))
    )
    (net (code "70") (name "Net-(X3D-KL)") (class "Default")
      (node (ref "Q1") (pin "D") (pinfunction "D_D") (pintype "passive"))
      (node (ref "X3") (pin "4") (pinfunction "KL_4") (pintype "passive"))
    )
    (net (code "71") (name "unconnected-(SW1-P-PadA)") (class "Default")
      (node (ref "SW1") (pin "A") (pinfunction "P_A") (pintype "passive"))
    )
    (net (code "72") (name "unconnected-(SW1-S-PadB)") (class "Default")
      (node (ref "SW1") (pin "B") (pinfunction "S_B") (pintype "passive"))
    )
    (net (code "73") (name "unconnected-(U1-0(RX0)-Pad0)") (class "Default")
      (node (ref "U1") (pin "0") (pinfunction "0(RX0)_0") (pintype "bidirectional"))
    )
    (net (code "74") (name "unconnected-(U1-1(TX0)-Pad1)") (class "Default")
      (node (ref "U1") (pin "1") (pinfunction "1(TX0)_1") (pintype "bidirectional"))
    )
    (net (code "75") (name "unconnected-(U1-5V-Pad5V@1)") (class "Default")
      (node (ref "U1") (pin "5V@1") (pinfunction "5V_5V@1") (pintype "bidirectional"))
    )
    (net (code "76") (name "unconnected-(U1-5V-Pad5V@2)") (class "Default")
      (node (ref "U1") (pin "5V@2") (pinfunction "5V_5V@2") (pintype "bidirectional"))
    )
    (net (code "77") (name "unconnected-(U1-16(TX2)-Pad16)") (class "Default")
      (node (ref "U1") (pin "16") (pinfunction "16(TX2)_16") (pintype "bidirectional"))
    )
    (net (code "78") (name "unconnected-(U1-17(RX2)-Pad17)") (class "Default")
      (node (ref "U1") (pin "17") (pinfunction "17(RX2)_17") (pintype "bidirectional"))
    )
    (net (code "79") (name "unconnected-(U1-A0(RX0)-PadA0)") (class "Default")
      (node (ref "U1") (pin "A0") (pinfunction "A0(RX0)_A0") (pintype "bidirectional"))
    )
    (net (code "80") (name "unconnected-(U1-A1(TX0)-PadA1)") (class "Default")
      (node (ref "U1") (pin "A1") (pinfunction "A1(TX0)_A1") (pintype "bidirectional"))
    )
    (net (code "81") (name "unconnected-(U1-GND-PadGND@0)") (class "Default")
      (node (ref "U1") (pin "GND@0") (pinfunction "GND_GND@0") (pintype "bidirectional"))
    )
    (net (code "82") (name "unconnected-(U1-GND-PadGND@1)") (class "Default")
      (node (ref "U1") (pin "GND@1") (pinfunction "GND_GND@1") (pintype "bidirectional"))
    )
    (net (code "83") (name "unconnected-(U1-GND-PadGND@2)") (class "Default")
      (node (ref "U1") (pin "GND@2") (pinfunction "GND_GND@2") (pintype "bidirectional"))
    )
    (net (code "84") (name "unconnected-(U1-GND-PadGND@3)") (class "Default")
      (node (ref "U1") (pin "GND@3") (pinfunction "GND_GND@3") (pintype "bidirectional"))
    )
    (net (code "85") (name "unconnected-(U1-Pad3.3V)") (class "Default")
      (node (ref "U1") (pin "3.3V") (pinfunction "3.3V_3.3V") (pintype "bidirectional"))
    )
    (net (code "86") (name "unconnected-(U1-Pad34)") (class "Default")
      (node (ref "U1") (pin "34") (pinfunction "34_34") (pintype "bidirectional"))
    )
    (net (code "87") (name "unconnected-(U1-Pad35)") (class "Default")
      (node (ref "U1") (pin "35") (pinfunction "35_35") (pintype "bidirectional"))
    )
    (net (code "88") (name "unconnected-(U1-Pad36)") (class "Default")
      (node (ref "U1") (pin "36") (pinfunction "36_36") (pintype "bidirectional"))
    )
    (net (code "89") (name "unconnected-(U1-Pad37)") (class "Default")
      (node (ref "U1") (pin "37") (pinfunction "37_37") (pintype "bidirectional"))
    )
    (net (code "90") (name "unconnected-(U1-Pad38)") (class "Default")
      (node (ref "U1") (pin "38") (pinfunction "38_38") (pintype "bidirectional"))
    )
    (net (code "91") (name "unconnected-(U1-Pad39)") (class "Default")
      (node (ref "U1") (pin "39") (pinfunction "39_39") (pintype "bidirectional"))
    )
    (net (code "92") (name "unconnected-(U1-Pad40)") (class "Default")
      (node (ref "U1") (pin "40") (pinfunction "40_40") (pintype "bidirectional"))
    )
    (net (code "93") (name "unconnected-(U1-Pad41)") (class "Default")
      (node (ref "U1") (pin "41") (pinfunction "41_41") (pintype "bidirectional"))
    )
    (net (code "94") (name "unconnected-(U1-Pad42)") (class "Default")
      (node (ref "U1") (pin "42") (pinfunction "42_42") (pintype "bidirectional"))
    )
    (net (code "95") (name "unconnected-(U1-Pad47)") (class "Default")
      (node (ref "U1") (pin "47") (pinfunction "47_47") (pintype "bidirectional"))
    )
    (net (code "96") (name "unconnected-(U1-Pad48)") (class "Default")
      (node (ref "U1") (pin "48") (pinfunction "48_48") (pintype "bidirectional"))
    )
    (net (code "97") (name "unconnected-(U1-Pad49)") (class "Default")
      (node (ref "U1") (pin "49") (pinfunction "49_49") (pintype "bidirectional"))
    )
    (net (code "98") (name "unconnected-(U1-Pad50)") (class "Default")
      (node (ref "U1") (pin "50") (pinfunction "50_50") (pintype "bidirectional"))
    )
    (net (code "99") (name "unconnected-(U1-Pad51)") (class "Default")
      (node (ref "U1") (pin "51") (pinfunction "51_51") (pintype "bidirectional"))
    )
    (net (code "100") (name "unconnected-(U1-Pad52)") (class "Default")
      (node (ref "U1") (pin "52") (pinfunction "52_52") (pintype "bidirectional"))
    )
    (net (code "101") (name "unconnected-(U1-Pad53)") (class "Default")
      (node (ref "U1") (pin "53") (pinfunction "53_53") (pintype "bidirectional"))
    )
    (net (code "102") (name "unconnected-(U1-PadA2)") (class "Default")
      (node (ref "U1") (pin "A2") (pinfunction "A2_A2") (pintype "bidirectional"))
    )
    (net (code "103") (name "unconnected-(U1-PadA3)") (class "Default")
      (node (ref "U1") (pin "A3") (pinfunction "A3_A3") (pintype "bidirectional"))
    )
    (net (code "104") (name "unconnected-(U1-PadA4)") (class "Default")
      (node (ref "U1") (pin "A4") (pinfunction "A4_A4") (pintype "bidirectional"))
    )
    (net (code "105") (name "unconnected-(U1-PadA5)") (class "Default")
      (node (ref "U1") (pin "A5") (pinfunction "A5_A5") (pintype "bidirectional"))
    )
    (net (code "106") (name "unconnected-(U1-PadA6)") (class "Default")
      (node (ref "U1") (pin "A6") (pinfunction "A6_A6") (pintype "bidirectional"))
    )
    (net (code "107") (name "unconnected-(U1-PadA7)") (class "Default")
      (node (ref "U1") (pin "A7") (pinfunction "A7_A7") (pintype "bidirectional"))
    )
    (net (code "108") (name "unconnected-(U1-PadA8)") (class "Default")
      (node (ref "U1") (pin "A8") (pinfunction "A8_A8") (pintype "bidirectional"))
    )
    (net (code "109") (name "unconnected-(U1-PadA9)") (class "Default")
      (node (ref "U1") (pin "A9") (pinfunction "A9_A9") (pintype "bidirectional"))
    )
    (net (code "110") (name "unconnected-(U1-PadA10)") (class "Default")
      (node (ref "U1") (pin "A10") (pinfunction "A10_A10") (pintype "bidirectional"))
    )
    (net (code "111") (name "unconnected-(U1-PadA11)") (class "Default")
      (node (ref "U1") (pin "A11") (pinfunction "A11_A11") (pintype "bidirectional"))
    )
    (net (code "112") (name "unconnected-(U1-PadA12)") (class "Default")
      (node (ref "U1") (pin "A12") (pinfunction "A12_A12") (pintype "bidirectional"))
    )
    (net (code "113") (name "unconnected-(U1-PadA13)") (class "Default")
      (node (ref "U1") (pin "A13") (pinfunction "A13_A13") (pintype "bidirectional"))
    )
    (net (code "114") (name "unconnected-(U1-PadA14)") (class "Default")
      (node (ref "U1") (pin "A14") (pinfunction "A14_A14") (pintype "bidirectional"))
    )
    (net (code "115") (name "unconnected-(U1-PadA15)") (class "Default")
      (node (ref "U1") (pin "A15") (pinfunction "A15_A15") (pintype "bidirectional"))
    )
    (net (code "116") (name "unconnected-(U1-PadAREF)") (class "Default")
      (node (ref "U1") (pin "AREF") (pinfunction "AREF_AREF") (pintype "bidirectional"))
    )
    (net (code "117") (name "unconnected-(X1-Pad37)") (class "Default")
      (node (ref "X1") (pin "37") (pinfunction "37_37") (pintype "passive"))
    )
    (net (code "118") (name "unconnected-(X1-Pad38)") (class "Default")
      (node (ref "X1") (pin "38") (pinfunction "38_38") (pintype "passive"))
    )
    (net (code "119") (name "unconnected-(X1-Pad39)") (class "Default")
      (node (ref "X1") (pin "39") (pinfunction "39_39") (pintype "passive"))
    )
    (net (code "120") (name "unconnected-(X1-Pad40)") (class "Default")
      (node (ref "X1") (pin "40") (pinfunction "40_40") (pintype "passive"))
    )
    (net (code "121") (name "unconnected-(X1-Pad41)") (class "Default")
      (node (ref "X1") (pin "41") (pinfunction "41_41") (pintype "passive"))
    )
    (net (code "122") (name "unconnected-(X1-Pad42)") (class "Default")
      (node (ref "X1") (pin "42") (pinfunction "42_42") (pintype "passive"))
    )
    (net (code "123") (name "unconnected-(X1-Pad43)") (class "Default")
      (node (ref "X1") (pin "43") (pinfunction "43_43") (pintype "passive"))
    )
    (net (code "124") (name "unconnected-(X1-Pad44)") (class "Default")
      (node (ref "X1") (pin "44") (pinfunction "44_44") (pintype "passive"))
    )
  )
)
